# Executive_230V_C.net
KiCad netlist of a schematic drawn in EAGLE
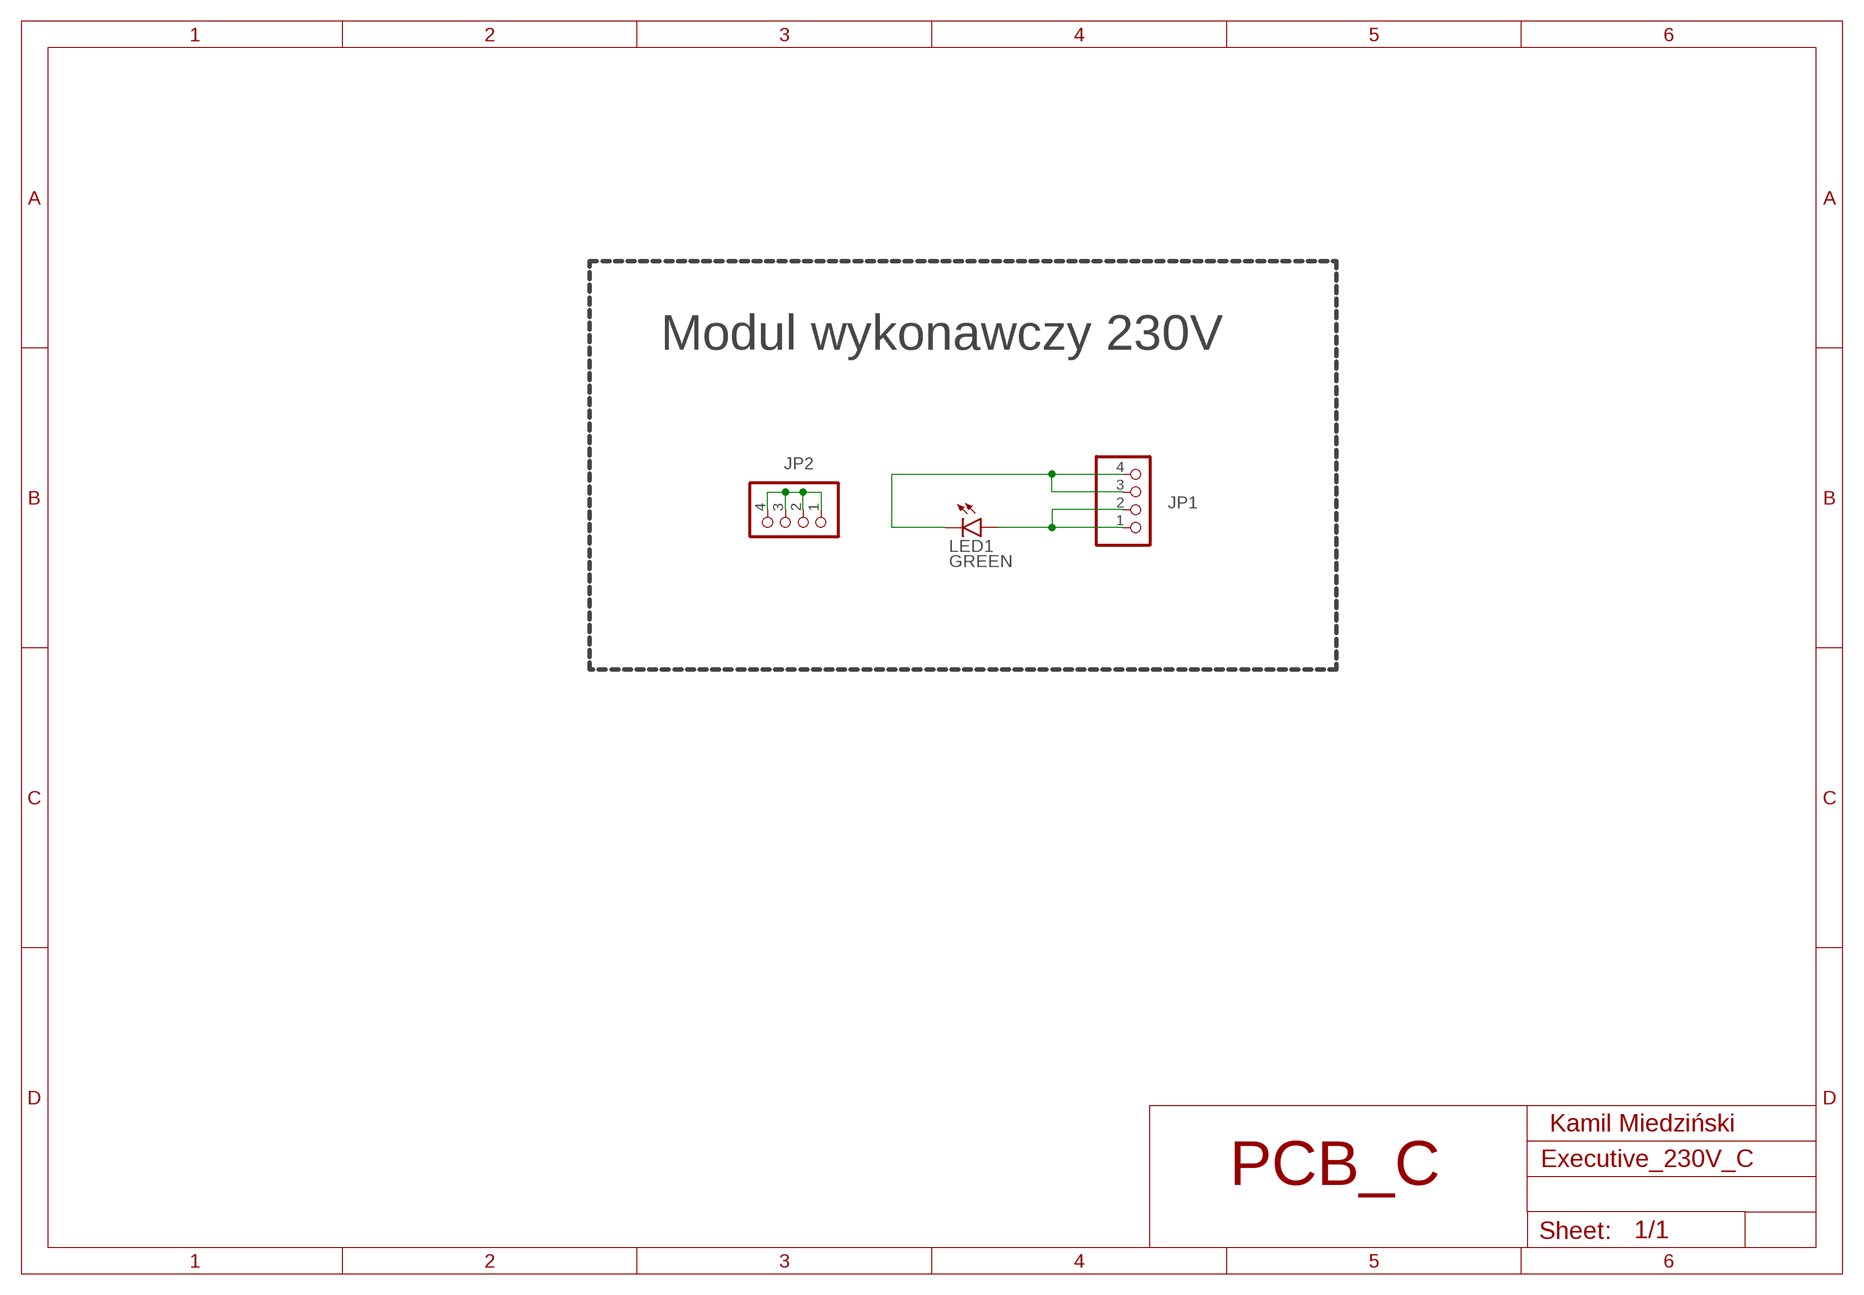
[diagram p0: schematic, sheet 1]

(export (version "E")
  (design (tool "Eeschema 10.0.6"))
  (components
    (comp (ref "JP1")
      (value "PINHD-1X41X04H")
      (footprint "eagle-import:1X04H")
      (libsource (lib "eagle-import") (part "PINHD-1X41X04H"))
    )
    (comp (ref "JP2")
      (value "PINHD-1X41X04H")
      (footprint "eagle-import:1X04H")
      (libsource (lib "eagle-import") (part "PINHD-1X41X04H"))
    )
    (comp (ref "LED1")
      (value "GREEN")
      (footprint "eagle-import:LED5MM_GREEN")
      (libsource (lib "eagle-import") (part "LED5MM_GREEN"))
    )
  )
  (nets
    (net (code "1") (name "Net-(JP1-Pad1)") (class "Default")
      (node (ref "JP1") (pin "1") (pinfunction "1_1") (pintype "passive"))
      (node (ref "JP1") (pin "2") (pinfunction "2_2") (pintype "passive"))
      (node (ref "LED1") (pin "A") (pinfunction "A_A") (pintype "passive"))
    )
    (net (code "2") (name "Net-(JP2-Pad1)") (class "Default")
      (node (ref "JP2") (pin "1") (pinfunction "1_1") (pintype "passive"))
      (node (ref "JP2") (pin "2") (pinfunction "2_2") (pintype "passive"))
      (node (ref "JP2") (pin "3") (pinfunction "3_3") (pintype "passive"))
      (node (ref "JP2") (pin "4") (pinfunction "4_4") (pintype "passive"))
    )
    (net (code "3") (name "Net-(LED1-C)") (class "Default")
      (node (ref "JP1") (pin "3") (pinfunction "3_3") (pintype "passive"))
      (node (ref "JP1") (pin "4") (pinfunction "4_4") (pintype "passive"))
      (node (ref "LED1") (pin "K") (pinfunction "C_K") (pintype "passive"))
    )
  )
)
